# PiKVM_ATX_Adapter_v1.net
KiCad netlist of a schematic drawn in EAGLE
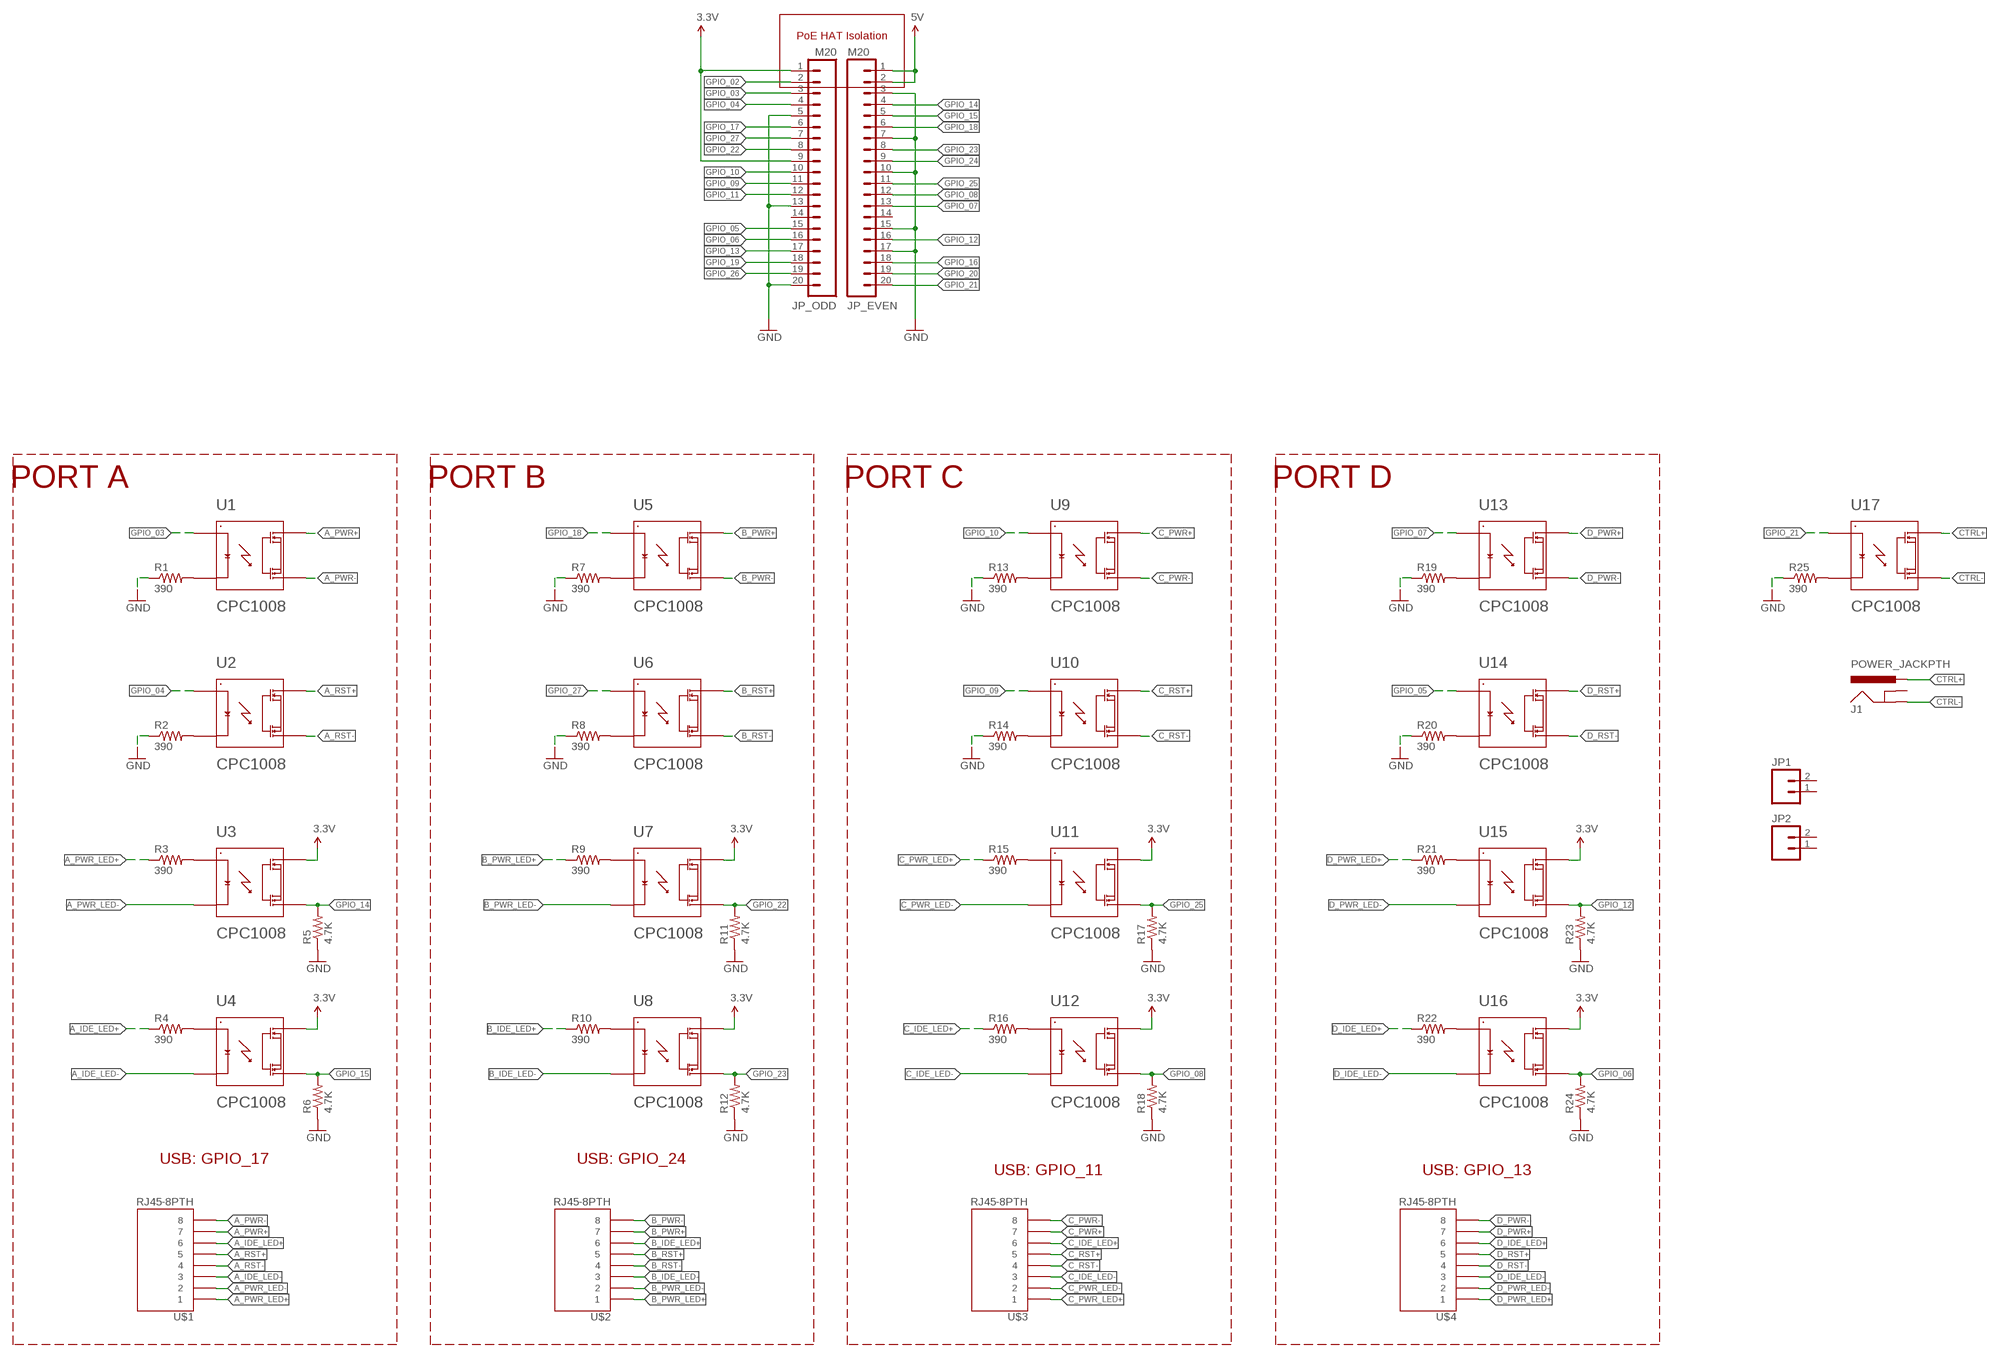
[diagram p0: schematic, sheet 1]

(export (version "E")
  (design (tool "Eeschema 10.0.6"))
  (components
    (comp (ref "J1")
      (value "POWER_JACKPTH")
      (footprint "eagle-import:POWER_JACK_PTH")
      (libsource (lib "eagle-import") (part "POWER_JACKPTH"))
    )
    (comp (ref "JP1")
      (value "M02LOCK")
      (footprint "eagle-import:1X02_LOCK")
      (libsource (lib "eagle-import") (part "M02LOCK"))
    )
    (comp (ref "JP2")
      (value "M02LOCK")
      (footprint "eagle-import:1X02_LOCK")
      (libsource (lib "eagle-import") (part "M02LOCK"))
    )
    (comp (ref "JP_EVEN")
      (value "M20")
      (footprint "eagle-import:1X20")
      (libsource (lib "eagle-import") (part "M20"))
    )
    (comp (ref "JP_ODD")
      (value "M20")
      (footprint "eagle-import:1X20")
      (libsource (lib "eagle-import") (part "M20"))
    )
    (comp (ref "R1")
      (value "390")
      (footprint "eagle-import:1206")
      (libsource (lib "eagle-import") (part "RESISTOR1206"))
    )
    (comp (ref "R2")
      (value "390")
      (footprint "eagle-import:1206")
      (libsource (lib "eagle-import") (part "RESISTOR1206"))
    )
    (comp (ref "R3")
      (value "390")
      (footprint "eagle-import:1206")
      (libsource (lib "eagle-import") (part "RESISTOR1206"))
    )
    (comp (ref "R4")
      (value "390")
      (footprint "eagle-import:1206")
      (libsource (lib "eagle-import") (part "RESISTOR1206"))
    )
    (comp (ref "R5")
      (value "4.7K")
      (footprint "eagle-import:1206")
      (libsource (lib "eagle-import") (part "RESISTOR1206"))
    )
    (comp (ref "R6")
      (value "4.7K")
      (footprint "eagle-import:1206")
      (libsource (lib "eagle-import") (part "RESISTOR1206"))
    )
    (comp (ref "R7")
      (value "390")
      (footprint "eagle-import:1206")
      (libsource (lib "eagle-import") (part "RESISTOR1206"))
    )
    (comp (ref "R8")
      (value "390")
      (footprint "eagle-import:1206")
      (libsource (lib "eagle-import") (part "RESISTOR1206"))
    )
    (comp (ref "R9")
      (value "390")
      (footprint "eagle-import:1206")
      (libsource (lib "eagle-import") (part "RESISTOR1206"))
    )
    (comp (ref "R10")
      (value "390")
      (footprint "eagle-import:1206")
      (libsource (lib "eagle-import") (part "RESISTOR1206"))
    )
    (comp (ref "R11")
      (value "4.7K")
      (footprint "eagle-import:1206")
      (libsource (lib "eagle-import") (part "RESISTOR1206"))
    )
    (comp (ref "R12")
      (value "4.7K")
      (footprint "eagle-import:1206")
      (libsource (lib "eagle-import") (part "RESISTOR1206"))
    )
    (comp (ref "R13")
      (value "390")
      (footprint "eagle-import:1206")
      (libsource (lib "eagle-import") (part "RESISTOR1206"))
    )
    (comp (ref "R14")
      (value "390")
      (footprint "eagle-import:1206")
      (libsource (lib "eagle-import") (part "RESISTOR1206"))
    )
    (comp (ref "R15")
      (value "390")
      (footprint "eagle-import:1206")
      (libsource (lib "eagle-import") (part "RESISTOR1206"))
    )
    (comp (ref "R16")
      (value "390")
      (footprint "eagle-import:1206")
      (libsource (lib "eagle-import") (part "RESISTOR1206"))
    )
    (comp (ref "R17")
      (value "4.7K")
      (footprint "eagle-import:1206")
      (libsource (lib "eagle-import") (part "RESISTOR1206"))
    )
    (comp (ref "R18")
      (value "4.7K")
      (footprint "eagle-import:1206")
      (libsource (lib "eagle-import") (part "RESISTOR1206"))
    )
    (comp (ref "R19")
      (value "390")
      (footprint "eagle-import:1206")
      (libsource (lib "eagle-import") (part "RESISTOR1206"))
    )
    (comp (ref "R20")
      (value "390")
      (footprint "eagle-import:1206")
      (libsource (lib "eagle-import") (part "RESISTOR1206"))
    )
    (comp (ref "R21")
      (value "390")
      (footprint "eagle-import:1206")
      (libsource (lib "eagle-import") (part "RESISTOR1206"))
    )
    (comp (ref "R22")
      (value "390")
      (footprint "eagle-import:1206")
      (libsource (lib "eagle-import") (part "RESISTOR1206"))
    )
    (comp (ref "R23")
      (value "4.7K")
      (footprint "eagle-import:1206")
      (libsource (lib "eagle-import") (part "RESISTOR1206"))
    )
    (comp (ref "R24")
      (value "4.7K")
      (footprint "eagle-import:1206")
      (libsource (lib "eagle-import") (part "RESISTOR1206"))
    )
    (comp (ref "R25")
      (value "390")
      (footprint "eagle-import:1206")
      (libsource (lib "eagle-import") (part "RESISTOR1206"))
    )
    (comp (ref "U$1")
      (value "RJ45-8PTH")
      (footprint "eagle-import:RJ45-8")
      (libsource (lib "eagle-import") (part "RJ45-8PTH"))
    )
    (comp (ref "U$2")
      (value "RJ45-8PTH")
      (footprint "eagle-import:RJ45-8")
      (libsource (lib "eagle-import") (part "RJ45-8PTH"))
    )
    (comp (ref "U$3")
      (value "RJ45-8PTH")
      (footprint "eagle-import:RJ45-8")
      (libsource (lib "eagle-import") (part "RJ45-8PTH"))
    )
    (comp (ref "U$4")
      (value "RJ45-8PTH")
      (footprint "eagle-import:RJ45-8")
      (libsource (lib "eagle-import") (part "RJ45-8PTH"))
    )
    (comp (ref "U1")
      (value "CPC1008")
      (footprint "eagle-import:SOP-4")
      (libsource (lib "eagle-import") (part "CPC1008"))
    )
    (comp (ref "U2")
      (value "CPC1008")
      (footprint "eagle-import:SOP-4")
      (libsource (lib "eagle-import") (part "CPC1008"))
    )
    (comp (ref "U3")
      (value "CPC1008")
      (footprint "eagle-import:SOP-4")
      (libsource (lib "eagle-import") (part "CPC1008"))
    )
    (comp (ref "U4")
      (value "CPC1008")
      (footprint "eagle-import:SOP-4")
      (libsource (lib "eagle-import") (part "CPC1008"))
    )
    (comp (ref "U5")
      (value "CPC1008")
      (footprint "eagle-import:SOP-4")
      (libsource (lib "eagle-import") (part "CPC1008"))
    )
    (comp (ref "U6")
      (value "CPC1008")
      (footprint "eagle-import:SOP-4")
      (libsource (lib "eagle-import") (part "CPC1008"))
    )
    (comp (ref "U7")
      (value "CPC1008")
      (footprint "eagle-import:SOP-4")
      (libsource (lib "eagle-import") (part "CPC1008"))
    )
    (comp (ref "U8")
      (value "CPC1008")
      (footprint "eagle-import:SOP-4")
      (libsource (lib "eagle-import") (part "CPC1008"))
    )
    (comp (ref "U9")
      (value "CPC1008")
      (footprint "eagle-import:SOP-4")
      (libsource (lib "eagle-import") (part "CPC1008"))
    )
    (comp (ref "U10")
      (value "CPC1008")
      (footprint "eagle-import:SOP-4")
      (libsource (lib "eagle-import") (part "CPC1008"))
    )
    (comp (ref "U11")
      (value "CPC1008")
      (footprint "eagle-import:SOP-4")
      (libsource (lib "eagle-import") (part "CPC1008"))
    )
    (comp (ref "U12")
      (value "CPC1008")
      (footprint "eagle-import:SOP-4")
      (libsource (lib "eagle-import") (part "CPC1008"))
    )
    (comp (ref "U13")
      (value "CPC1008")
      (footprint "eagle-import:SOP-4")
      (libsource (lib "eagle-import") (part "CPC1008"))
    )
    (comp (ref "U14")
      (value "CPC1008")
      (footprint "eagle-import:SOP-4")
      (libsource (lib "eagle-import") (part "CPC1008"))
    )
    (comp (ref "U15")
      (value "CPC1008")
      (footprint "eagle-import:SOP-4")
      (libsource (lib "eagle-import") (part "CPC1008"))
    )
    (comp (ref "U16")
      (value "CPC1008")
      (footprint "eagle-import:SOP-4")
      (libsource (lib "eagle-import") (part "CPC1008"))
    )
    (comp (ref "U17")
      (value "CPC1008")
      (footprint "eagle-import:SOP-4")
      (libsource (lib "eagle-import") (part "CPC1008"))
    )
  )
  (nets
    (net (code "1") (name "3.3V") (class "Default")
      (node (ref "JP_ODD") (pin "1") (pinfunction "1_1") (pintype "passive"))
      (node (ref "JP_ODD") (pin "9") (pinfunction "9_9") (pintype "passive"))
      (node (ref "U11") (pin "P$4") (pinfunction "4_P$4") (pintype "bidirectional"))
      (node (ref "U12") (pin "P$4") (pinfunction "4_P$4") (pintype "bidirectional"))
      (node (ref "U15") (pin "P$4") (pinfunction "4_P$4") (pintype "bidirectional"))
      (node (ref "U16") (pin "P$4") (pinfunction "4_P$4") (pintype "bidirectional"))
      (node (ref "U3") (pin "P$4") (pinfunction "4_P$4") (pintype "bidirectional"))
      (node (ref "U4") (pin "P$4") (pinfunction "4_P$4") (pintype "bidirectional"))
      (node (ref "U7") (pin "P$4") (pinfunction "4_P$4") (pintype "bidirectional"))
      (node (ref "U8") (pin "P$4") (pinfunction "4_P$4") (pintype "bidirectional"))
    )
    (net (code "2") (name "5V") (class "Default")
      (node (ref "JP_EVEN") (pin "1") (pinfunction "1_1") (pintype "passive"))
      (node (ref "JP_EVEN") (pin "2") (pinfunction "2_2") (pintype "passive"))
    )
    (net (code "3") (name "A_IDE_LED+") (class "Default")
      (node (ref "R4") (pin "1") (pinfunction "1_1") (pintype "passive"))
      (node (ref "U$1") (pin "6") (pinfunction "6_6") (pintype "bidirectional"))
    )
    (net (code "4") (name "A_IDE_LED-") (class "Default")
      (node (ref "U$1") (pin "3") (pinfunction "3_3") (pintype "bidirectional"))
      (node (ref "U4") (pin "P$2") (pinfunction "2_P$2") (pintype "bidirectional"))
    )
    (net (code "5") (name "A_PWR+") (class "Default")
      (node (ref "U$1") (pin "7") (pinfunction "7_7") (pintype "bidirectional"))
      (node (ref "U1") (pin "P$4") (pinfunction "4_P$4") (pintype "bidirectional"))
    )
    (net (code "6") (name "A_PWR-") (class "Default")
      (node (ref "U$1") (pin "8") (pinfunction "8_8") (pintype "bidirectional"))
      (node (ref "U1") (pin "P$3") (pinfunction "3_P$3") (pintype "bidirectional"))
    )
    (net (code "7") (name "A_PWR_LED+") (class "Default")
      (node (ref "R3") (pin "1") (pinfunction "1_1") (pintype "passive"))
      (node (ref "U$1") (pin "1") (pinfunction "1_1") (pintype "bidirectional"))
    )
    (net (code "8") (name "A_PWR_LED-") (class "Default")
      (node (ref "U$1") (pin "2") (pinfunction "2_2") (pintype "bidirectional"))
      (node (ref "U3") (pin "P$2") (pinfunction "2_P$2") (pintype "bidirectional"))
    )
    (net (code "9") (name "A_RST+") (class "Default")
      (node (ref "U$1") (pin "5") (pinfunction "5_5") (pintype "bidirectional"))
      (node (ref "U2") (pin "P$4") (pinfunction "4_P$4") (pintype "bidirectional"))
    )
    (net (code "10") (name "A_RST-") (class "Default")
      (node (ref "U$1") (pin "4") (pinfunction "4_4") (pintype "bidirectional"))
      (node (ref "U2") (pin "P$3") (pinfunction "3_P$3") (pintype "bidirectional"))
    )
    (net (code "11") (name "B_IDE_LED+") (class "Default")
      (node (ref "R10") (pin "1") (pinfunction "1_1") (pintype "passive"))
      (node (ref "U$2") (pin "6") (pinfunction "6_6") (pintype "bidirectional"))
    )
    (net (code "12") (name "B_IDE_LED-") (class "Default")
      (node (ref "U$2") (pin "3") (pinfunction "3_3") (pintype "bidirectional"))
      (node (ref "U8") (pin "P$2") (pinfunction "2_P$2") (pintype "bidirectional"))
    )
    (net (code "13") (name "B_PWR+") (class "Default")
      (node (ref "U$2") (pin "7") (pinfunction "7_7") (pintype "bidirectional"))
      (node (ref "U5") (pin "P$4") (pinfunction "4_P$4") (pintype "bidirectional"))
    )
    (net (code "14") (name "B_PWR-") (class "Default")
      (node (ref "U$2") (pin "8") (pinfunction "8_8") (pintype "bidirectional"))
      (node (ref "U5") (pin "P$3") (pinfunction "3_P$3") (pintype "bidirectional"))
    )
    (net (code "15") (name "B_PWR_LED+") (class "Default")
      (node (ref "R9") (pin "1") (pinfunction "1_1") (pintype "passive"))
      (node (ref "U$2") (pin "1") (pinfunction "1_1") (pintype "bidirectional"))
    )
    (net (code "16") (name "B_PWR_LED-") (class "Default")
      (node (ref "U$2") (pin "2") (pinfunction "2_2") (pintype "bidirectional"))
      (node (ref "U7") (pin "P$2") (pinfunction "2_P$2") (pintype "bidirectional"))
    )
    (net (code "17") (name "B_RST+") (class "Default")
      (node (ref "U$2") (pin "5") (pinfunction "5_5") (pintype "bidirectional"))
      (node (ref "U6") (pin "P$4") (pinfunction "4_P$4") (pintype "bidirectional"))
    )
    (net (code "18") (name "B_RST-") (class "Default")
      (node (ref "U$2") (pin "4") (pinfunction "4_4") (pintype "bidirectional"))
      (node (ref "U6") (pin "P$3") (pinfunction "3_P$3") (pintype "bidirectional"))
    )
    (net (code "19") (name "CTRL+") (class "Default")
      (node (ref "J1") (pin "PWR") (pinfunction "PWR_PWR") (pintype "bidirectional"))
      (node (ref "U17") (pin "P$4") (pinfunction "4_P$4") (pintype "bidirectional"))
    )
    (net (code "20") (name "CTRL-") (class "Default")
      (node (ref "J1") (pin "GND") (pinfunction "GND_GND") (pintype "bidirectional"))
      (node (ref "U17") (pin "P$3") (pinfunction "3_P$3") (pintype "bidirectional"))
    )
    (net (code "21") (name "C_IDE_LED+") (class "Default")
      (node (ref "R16") (pin "1") (pinfunction "1_1") (pintype "passive"))
      (node (ref "U$3") (pin "6") (pinfunction "6_6") (pintype "bidirectional"))
    )
    (net (code "22") (name "C_IDE_LED-") (class "Default")
      (node (ref "U$3") (pin "3") (pinfunction "3_3") (pintype "bidirectional"))
      (node (ref "U12") (pin "P$2") (pinfunction "2_P$2") (pintype "bidirectional"))
    )
    (net (code "23") (name "C_PWR+") (class "Default")
      (node (ref "U$3") (pin "7") (pinfunction "7_7") (pintype "bidirectional"))
      (node (ref "U9") (pin "P$4") (pinfunction "4_P$4") (pintype "bidirectional"))
    )
    (net (code "24") (name "C_PWR-") (class "Default")
      (node (ref "U$3") (pin "8") (pinfunction "8_8") (pintype "bidirectional"))
      (node (ref "U9") (pin "P$3") (pinfunction "3_P$3") (pintype "bidirectional"))
    )
    (net (code "25") (name "C_PWR_LED+") (class "Default")
      (node (ref "R15") (pin "1") (pinfunction "1_1") (pintype "passive"))
      (node (ref "U$3") (pin "1") (pinfunction "1_1") (pintype "bidirectional"))
    )
    (net (code "26") (name "C_PWR_LED-") (class "Default")
      (node (ref "U$3") (pin "2") (pinfunction "2_2") (pintype "bidirectional"))
      (node (ref "U11") (pin "P$2") (pinfunction "2_P$2") (pintype "bidirectional"))
    )
    (net (code "27") (name "C_RST+") (class "Default")
      (node (ref "U$3") (pin "5") (pinfunction "5_5") (pintype "bidirectional"))
      (node (ref "U10") (pin "P$4") (pinfunction "4_P$4") (pintype "bidirectional"))
    )
    (net (code "28") (name "C_RST-") (class "Default")
      (node (ref "U$3") (pin "4") (pinfunction "4_4") (pintype "bidirectional"))
      (node (ref "U10") (pin "P$3") (pinfunction "3_P$3") (pintype "bidirectional"))
    )
    (net (code "29") (name "D_IDE_LED+") (class "Default")
      (node (ref "R22") (pin "1") (pinfunction "1_1") (pintype "passive"))
      (node (ref "U$4") (pin "6") (pinfunction "6_6") (pintype "bidirectional"))
    )
    (net (code "30") (name "D_IDE_LED-") (class "Default")
      (node (ref "U$4") (pin "3") (pinfunction "3_3") (pintype "bidirectional"))
      (node (ref "U16") (pin "P$2") (pinfunction "2_P$2") (pintype "bidirectional"))
    )
    (net (code "31") (name "D_PWR+") (class "Default")
      (node (ref "U$4") (pin "7") (pinfunction "7_7") (pintype "bidirectional"))
      (node (ref "U13") (pin "P$4") (pinfunction "4_P$4") (pintype "bidirectional"))
    )
    (net (code "32") (name "D_PWR-") (class "Default")
      (node (ref "U$4") (pin "8") (pinfunction "8_8") (pintype "bidirectional"))
      (node (ref "U13") (pin "P$3") (pinfunction "3_P$3") (pintype "bidirectional"))
    )
    (net (code "33") (name "D_PWR_LED+") (class "Default")
      (node (ref "R21") (pin "1") (pinfunction "1_1") (pintype "passive"))
      (node (ref "U$4") (pin "1") (pinfunction "1_1") (pintype "bidirectional"))
    )
    (net (code "34") (name "D_PWR_LED-") (class "Default")
      (node (ref "U$4") (pin "2") (pinfunction "2_2") (pintype "bidirectional"))
      (node (ref "U15") (pin "P$2") (pinfunction "2_P$2") (pintype "bidirectional"))
    )
    (net (code "35") (name "D_RST+") (class "Default")
      (node (ref "U$4") (pin "5") (pinfunction "5_5") (pintype "bidirectional"))
      (node (ref "U14") (pin "P$4") (pinfunction "4_P$4") (pintype "bidirectional"))
    )
    (net (code "36") (name "D_RST-") (class "Default")
      (node (ref "U$4") (pin "4") (pinfunction "4_4") (pintype "bidirectional"))
      (node (ref "U14") (pin "P$3") (pinfunction "3_P$3") (pintype "bidirectional"))
    )
    (net (code "37") (name "GND") (class "Default")
      (node (ref "JP_EVEN") (pin "10") (pinfunction "10_10") (pintype "passive"))
      (node (ref "JP_EVEN") (pin "15") (pinfunction "15_15") (pintype "passive"))
      (node (ref "JP_EVEN") (pin "17") (pinfunction "17_17") (pintype "passive"))
      (node (ref "JP_EVEN") (pin "3") (pinfunction "3_3") (pintype "passive"))
      (node (ref "JP_EVEN") (pin "7") (pinfunction "7_7") (pintype "passive"))
      (node (ref "JP_ODD") (pin "13") (pinfunction "13_13") (pintype "passive"))
      (node (ref "JP_ODD") (pin "20") (pinfunction "20_20") (pintype "passive"))
      (node (ref "JP_ODD") (pin "5") (pinfunction "5_5") (pintype "passive"))
      (node (ref "R1") (pin "1") (pinfunction "1_1") (pintype "passive"))
      (node (ref "R11") (pin "1") (pinfunction "1_1") (pintype "passive"))
      (node (ref "R12") (pin "1") (pinfunction "1_1") (pintype "passive"))
      (node (ref "R13") (pin "1") (pinfunction "1_1") (pintype "passive"))
      (node (ref "R14") (pin "1") (pinfunction "1_1") (pintype "passive"))
      (node (ref "R17") (pin "1") (pinfunction "1_1") (pintype "passive"))
      (node (ref "R18") (pin "1") (pinfunction "1_1") (pintype "passive"))
      (node (ref "R19") (pin "1") (pinfunction "1_1") (pintype "passive"))
      (node (ref "R2") (pin "1") (pinfunction "1_1") (pintype "passive"))
      (node (ref "R20") (pin "1") (pinfunction "1_1") (pintype "passive"))
      (node (ref "R23") (pin "1") (pinfunction "1_1") (pintype "passive"))
      (node (ref "R24") (pin "1") (pinfunction "1_1") (pintype "passive"))
      (node (ref "R25") (pin "1") (pinfunction "1_1") (pintype "passive"))
      (node (ref "R5") (pin "1") (pinfunction "1_1") (pintype "passive"))
      (node (ref "R6") (pin "1") (pinfunction "1_1") (pintype "passive"))
      (node (ref "R7") (pin "1") (pinfunction "1_1") (pintype "passive"))
      (node (ref "R8") (pin "1") (pinfunction "1_1") (pintype "passive"))
    )
    (net (code "38") (name "GPIO_02") (class "Default")
      (node (ref "JP_ODD") (pin "2") (pinfunction "2_2") (pintype "passive"))
    )
    (net (code "39") (name "GPIO_03") (class "Default")
      (node (ref "JP_ODD") (pin "3") (pinfunction "3_3") (pintype "passive"))
      (node (ref "U1") (pin "P$1") (pinfunction "1_P$1") (pintype "bidirectional"))
    )
    (net (code "40") (name "GPIO_04") (class "Default")
      (node (ref "JP_ODD") (pin "4") (pinfunction "4_4") (pintype "passive"))
      (node (ref "U2") (pin "P$1") (pinfunction "1_P$1") (pintype "bidirectional"))
    )
    (net (code "41") (name "GPIO_05") (class "Default")
      (node (ref "JP_ODD") (pin "15") (pinfunction "15_15") (pintype "passive"))
      (node (ref "U14") (pin "P$1") (pinfunction "1_P$1") (pintype "bidirectional"))
    )
    (net (code "42") (name "GPIO_06") (class "Default")
      (node (ref "JP_ODD") (pin "16") (pinfunction "16_16") (pintype "passive"))
      (node (ref "R24") (pin "2") (pinfunction "2_2") (pintype "passive"))
      (node (ref "U16") (pin "P$3") (pinfunction "3_P$3") (pintype "bidirectional"))
    )
    (net (code "43") (name "GPIO_07") (class "Default")
      (node (ref "JP_EVEN") (pin "13") (pinfunction "13_13") (pintype "passive"))
      (node (ref "U13") (pin "P$1") (pinfunction "1_P$1") (pintype "bidirectional"))
    )
    (net (code "44") (name "GPIO_08") (class "Default")
      (node (ref "JP_EVEN") (pin "12") (pinfunction "12_12") (pintype "passive"))
      (node (ref "R18") (pin "2") (pinfunction "2_2") (pintype "passive"))
      (node (ref "U12") (pin "P$3") (pinfunction "3_P$3") (pintype "bidirectional"))
    )
    (net (code "45") (name "GPIO_09") (class "Default")
      (node (ref "JP_ODD") (pin "11") (pinfunction "11_11") (pintype "passive"))
      (node (ref "U10") (pin "P$1") (pinfunction "1_P$1") (pintype "bidirectional"))
    )
    (net (code "46") (name "GPIO_10") (class "Default")
      (node (ref "JP_ODD") (pin "10") (pinfunction "10_10") (pintype "passive"))
      (node (ref "U9") (pin "P$1") (pinfunction "1_P$1") (pintype "bidirectional"))
    )
    (net (code "47") (name "GPIO_11") (class "Default")
      (node (ref "JP_ODD") (pin "12") (pinfunction "12_12") (pintype "passive"))
    )
    (net (code "48") (name "GPIO_12") (class "Default")
      (node (ref "JP_EVEN") (pin "16") (pinfunction "16_16") (pintype "passive"))
      (node (ref "R23") (pin "2") (pinfunction "2_2") (pintype "passive"))
      (node (ref "U15") (pin "P$3") (pinfunction "3_P$3") (pintype "bidirectional"))
    )
    (net (code "49") (name "GPIO_13") (class "Default")
      (node (ref "JP_ODD") (pin "17") (pinfunction "17_17") (pintype "passive"))
    )
    (net (code "50") (name "GPIO_14") (class "Default")
      (node (ref "JP_EVEN") (pin "4") (pinfunction "4_4") (pintype "passive"))
      (node (ref "R5") (pin "2") (pinfunction "2_2") (pintype "passive"))
      (node (ref "U3") (pin "P$3") (pinfunction "3_P$3") (pintype "bidirectional"))
    )
    (net (code "51") (name "GPIO_15") (class "Default")
      (node (ref "JP_EVEN") (pin "5") (pinfunction "5_5") (pintype "passive"))
      (node (ref "R6") (pin "2") (pinfunction "2_2") (pintype "passive"))
      (node (ref "U4") (pin "P$3") (pinfunction "3_P$3") (pintype "bidirectional"))
    )
    (net (code "52") (name "GPIO_16") (class "Default")
      (node (ref "JP_EVEN") (pin "18") (pinfunction "18_18") (pintype "passive"))
    )
    (net (code "53") (name "GPIO_17") (class "Default")
      (node (ref "JP_ODD") (pin "6") (pinfunction "6_6") (pintype "passive"))
    )
    (net (code "54") (name "GPIO_18") (class "Default")
      (node (ref "JP_EVEN") (pin "6") (pinfunction "6_6") (pintype "passive"))
      (node (ref "U5") (pin "P$1") (pinfunction "1_P$1") (pintype "bidirectional"))
    )
    (net (code "55") (name "GPIO_19") (class "Default")
      (node (ref "JP_ODD") (pin "18") (pinfunction "18_18") (pintype "passive"))
    )
    (net (code "56") (name "GPIO_20") (class "Default")
      (node (ref "JP_EVEN") (pin "19") (pinfunction "19_19") (pintype "passive"))
    )
    (net (code "57") (name "GPIO_21") (class "Default")
      (node (ref "JP_EVEN") (pin "20") (pinfunction "20_20") (pintype "passive"))
      (node (ref "U17") (pin "P$1") (pinfunction "1_P$1") (pintype "bidirectional"))
    )
    (net (code "58") (name "GPIO_22") (class "Default")
      (node (ref "JP_ODD") (pin "8") (pinfunction "8_8") (pintype "passive"))
      (node (ref "R11") (pin "2") (pinfunction "2_2") (pintype "passive"))
      (node (ref "U7") (pin "P$3") (pinfunction "3_P$3") (pintype "bidirectional"))
    )
    (net (code "59") (name "GPIO_23") (class "Default")
      (node (ref "JP_EVEN") (pin "8") (pinfunction "8_8") (pintype "passive"))
      (node (ref "R12") (pin "2") (pinfunction "2_2") (pintype "passive"))
      (node (ref "U8") (pin "P$3") (pinfunction "3_P$3") (pintype "bidirectional"))
    )
    (net (code "60") (name "GPIO_24") (class "Default")
      (node (ref "JP_EVEN") (pin "9") (pinfunction "9_9") (pintype "passive"))
    )
    (net (code "61") (name "GPIO_25") (class "Default")
      (node (ref "JP_EVEN") (pin "11") (pinfunction "11_11") (pintype "passive"))
      (node (ref "R17") (pin "2") (pinfunction "2_2") (pintype "passive"))
      (node (ref "U11") (pin "P$3") (pinfunction "3_P$3") (pintype "bidirectional"))
    )
    (net (code "62") (name "GPIO_26") (class "Default")
      (node (ref "JP_ODD") (pin "19") (pinfunction "19_19") (pintype "passive"))
    )
    (net (code "63") (name "GPIO_27") (class "Default")
      (node (ref "JP_ODD") (pin "7") (pinfunction "7_7") (pintype "passive"))
      (node (ref "U6") (pin "P$1") (pinfunction "1_P$1") (pintype "bidirectional"))
    )
    (net (code "64") (name "Net-(U1-2)") (class "Default")
      (node (ref "R1") (pin "2") (pinfunction "2_2") (pintype "passive"))
      (node (ref "U1") (pin "P$2") (pinfunction "2_P$2") (pintype "bidirectional"))
    )
    (net (code "65") (name "Net-(U2-2)") (class "Default")
      (node (ref "R2") (pin "2") (pinfunction "2_2") (pintype "passive"))
      (node (ref "U2") (pin "P$2") (pinfunction "2_P$2") (pintype "bidirectional"))
    )
    (net (code "66") (name "Net-(U3-1)") (class "Default")
      (node (ref "R3") (pin "2") (pinfunction "2_2") (pintype "passive"))
      (node (ref "U3") (pin "P$1") (pinfunction "1_P$1") (pintype "bidirectional"))
    )
    (net (code "67") (name "Net-(U4-1)") (class "Default")
      (node (ref "R4") (pin "2") (pinfunction "2_2") (pintype "passive"))
      (node (ref "U4") (pin "P$1") (pinfunction "1_P$1") (pintype "bidirectional"))
    )
    (net (code "68") (name "Net-(U5-2)") (class "Default")
      (node (ref "R7") (pin "2") (pinfunction "2_2") (pintype "passive"))
      (node (ref "U5") (pin "P$2") (pinfunction "2_P$2") (pintype "bidirectional"))
    )
    (net (code "69") (name "Net-(U6-2)") (class "Default")
      (node (ref "R8") (pin "2") (pinfunction "2_2") (pintype "passive"))
      (node (ref "U6") (pin "P$2") (pinfunction "2_P$2") (pintype "bidirectional"))
    )
    (net (code "70") (name "Net-(U7-1)") (class "Default")
      (node (ref "R9") (pin "2") (pinfunction "2_2") (pintype "passive"))
      (node (ref "U7") (pin "P$1") (pinfunction "1_P$1") (pintype "bidirectional"))
    )
    (net (code "71") (name "Net-(U8-1)") (class "Default")
      (node (ref "R10") (pin "2") (pinfunction "2_2") (pintype "passive"))
      (node (ref "U8") (pin "P$1") (pinfunction "1_P$1") (pintype "bidirectional"))
    )
    (net (code "72") (name "Net-(U9-2)") (class "Default")
      (node (ref "R13") (pin "2") (pinfunction "2_2") (pintype "passive"))
      (node (ref "U9") (pin "P$2") (pinfunction "2_P$2") (pintype "bidirectional"))
    )
    (net (code "73") (name "Net-(U10-2)") (class "Default")
      (node (ref "R14") (pin "2") (pinfunction "2_2") (pintype "passive"))
      (node (ref "U10") (pin "P$2") (pinfunction "2_P$2") (pintype "bidirectional"))
    )
    (net (code "74") (name "Net-(U11-1)") (class "Default")
      (node (ref "R15") (pin "2") (pinfunction "2_2") (pintype "passive"))
      (node (ref "U11") (pin "P$1") (pinfunction "1_P$1") (pintype "bidirectional"))
    )
    (net (code "75") (name "Net-(U12-1)") (class "Default")
      (node (ref "R16") (pin "2") (pinfunction "2_2") (pintype "passive"))
      (node (ref "U12") (pin "P$1") (pinfunction "1_P$1") (pintype "bidirectional"))
    )
    (net (code "76") (name "Net-(U13-2)") (class "Default")
      (node (ref "R19") (pin "2") (pinfunction "2_2") (pintype "passive"))
      (node (ref "U13") (pin "P$2") (pinfunction "2_P$2") (pintype "bidirectional"))
    )
    (net (code "77") (name "Net-(U14-2)") (class "Default")
      (node (ref "R20") (pin "2") (pinfunction "2_2") (pintype "passive"))
      (node (ref "U14") (pin "P$2") (pinfunction "2_P$2") (pintype "bidirectional"))
    )
    (net (code "78") (name "Net-(U15-1)") (class "Default")
      (node (ref "R21") (pin "2") (pinfunction "2_2") (pintype "passive"))
      (node (ref "U15") (pin "P$1") (pinfunction "1_P$1") (pintype "bidirectional"))
    )
    (net (code "79") (name "Net-(U16-1)") (class "Default")
      (node (ref "R22") (pin "2") (pinfunction "2_2") (pintype "passive"))
      (node (ref "U16") (pin "P$1") (pinfunction "1_P$1") (pintype "bidirectional"))
    )
    (net (code "80") (name "Net-(U17-2)") (class "Default")
      (node (ref "R25") (pin "2") (pinfunction "2_2") (pintype "passive"))
      (node (ref "U17") (pin "P$2") (pinfunction "2_P$2") (pintype "bidirectional"))
    )
    (net (code "81") (name "unconnected-(J1-PadGNDBREAK)") (class "Default")
      (node (ref "J1") (pin "GNDBREAK") (pinfunction "GNDBREAK_GNDBREAK") (pintype "bidirectional"))
    )
    (net (code "82") (name "unconnected-(JP1-Pad1)") (class "Default")
      (node (ref "JP1") (pin "1") (pinfunction "1_1") (pintype "passive"))
    )
    (net (code "83") (name "unconnected-(JP1-Pad2)") (class "Default")
      (node (ref "JP1") (pin "2") (pinfunction "2_2") (pintype "passive"))
    )
    (net (code "84") (name "unconnected-(JP2-Pad1)") (class "Default")
      (node (ref "JP2") (pin "1") (pinfunction "1_1") (pintype "passive"))
    )
    (net (code "85") (name "unconnected-(JP2-Pad2)") (class "Default")
      (node (ref "JP2") (pin "2") (pinfunction "2_2") (pintype "passive"))
    )
    (net (code "86") (name "unconnected-(JP_EVEN-Pad14)") (class "Default")
      (node (ref "JP_EVEN") (pin "14") (pinfunction "14_14") (pintype "passive"))
    )
    (net (code "87") (name "unconnected-(JP_ODD-Pad14)") (class "Default")
      (node (ref "JP_ODD") (pin "14") (pinfunction "14_14") (pintype "passive"))
    )
  )
)
